# SigfoxTracker.net
KiCad netlist of a schematic drawn in EAGLE
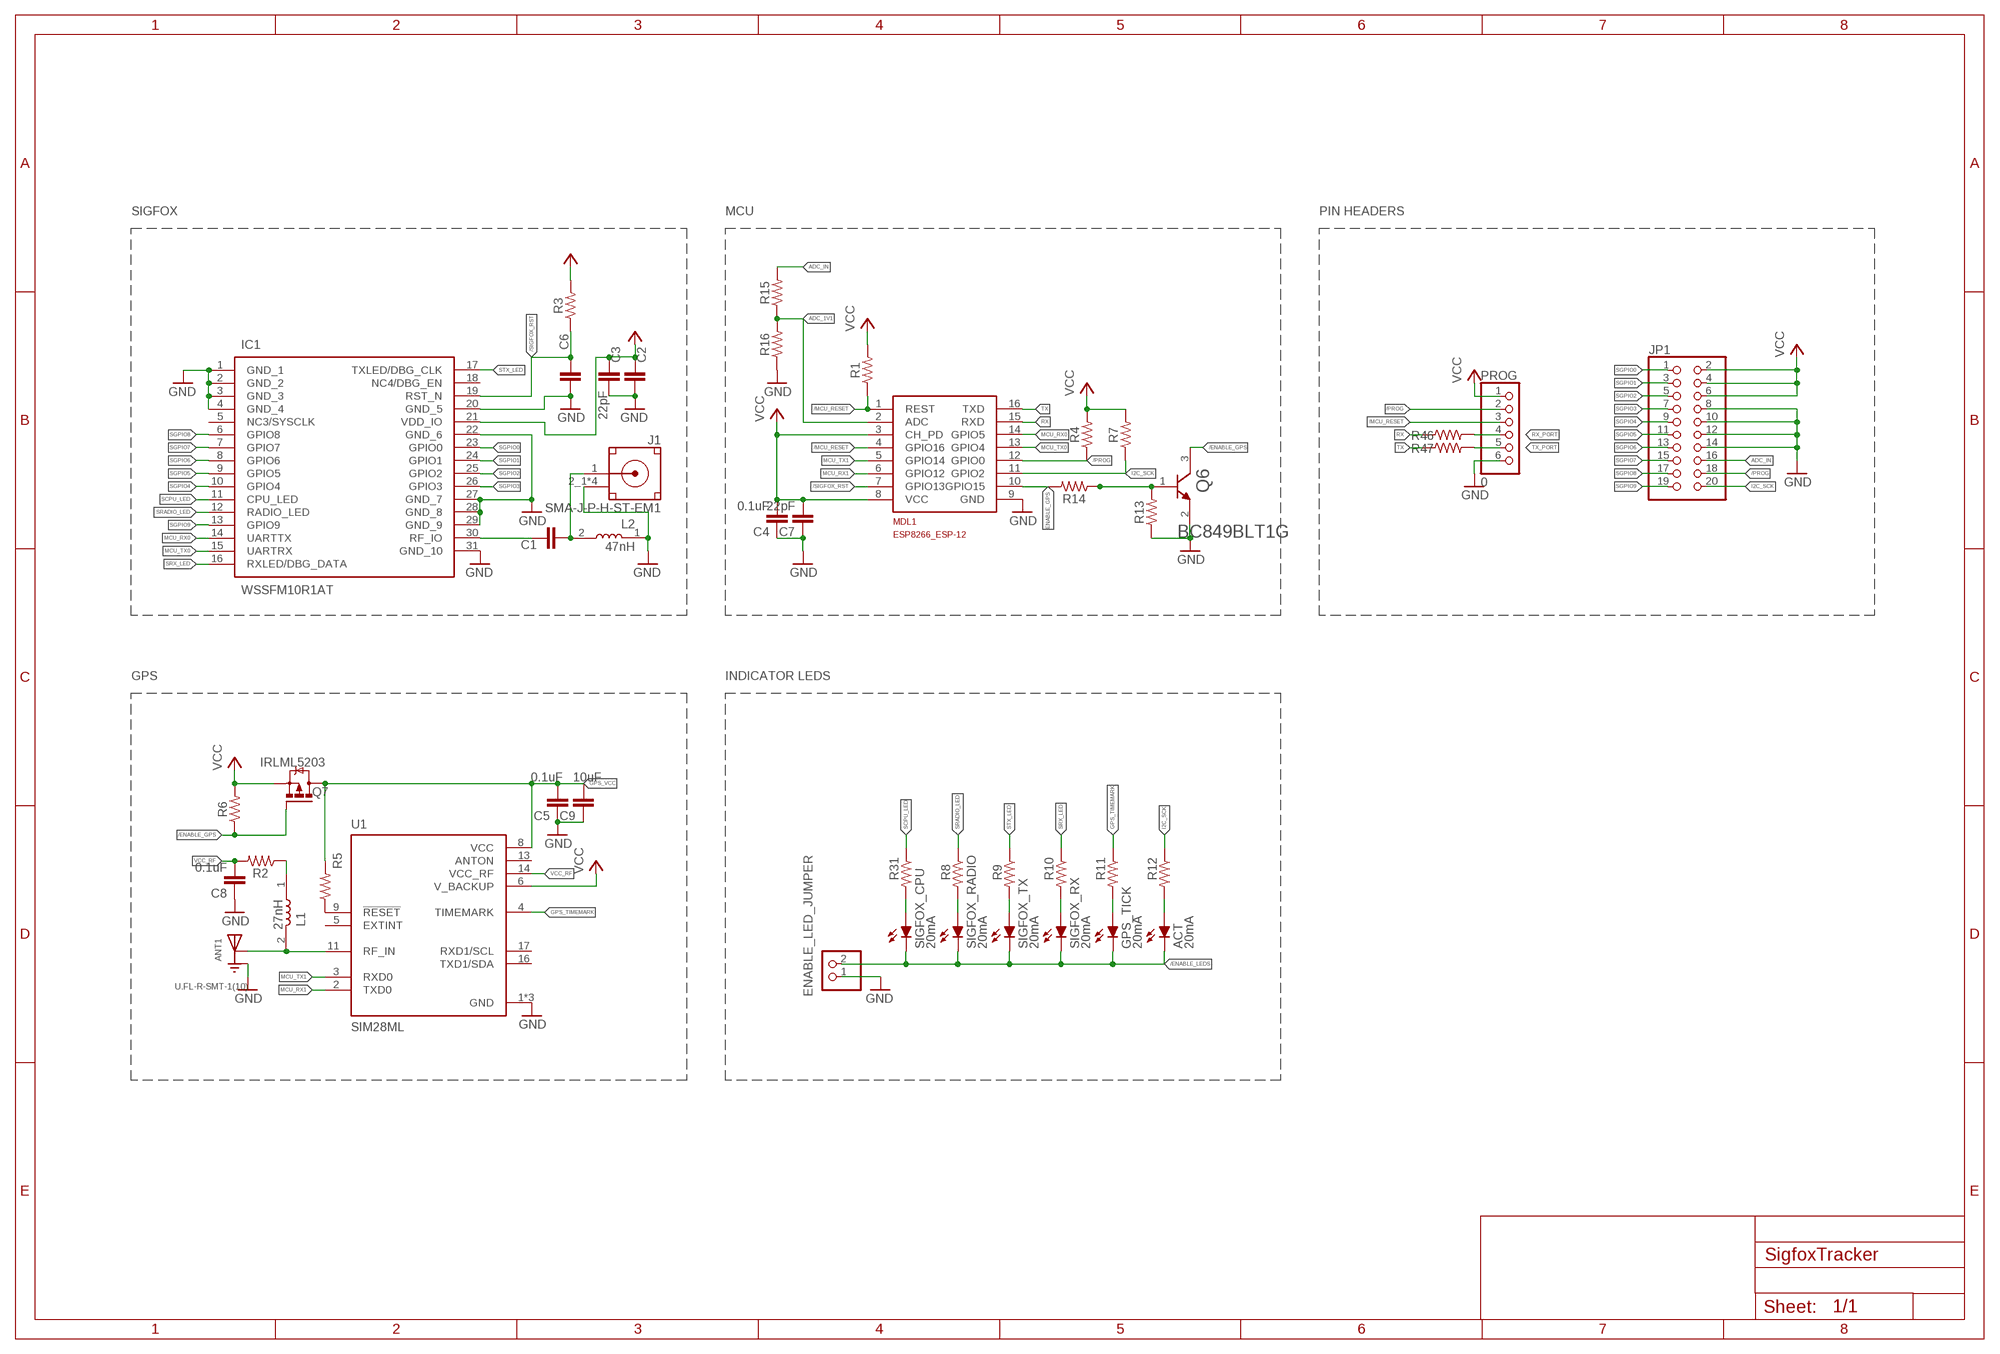
[diagram p0: schematic, sheet 1]

(export (version "E")
  (design (tool "Eeschema 10.0.6"))
  (components
    (comp (ref "ACT")
      (value "20mA")
      (footprint "eagle-import:LED_CHIP-LED0603MP")
      (libsource (lib "eagle-import") (part "LED_LEDCHIP-LED0603MP"))
    )
    (comp (ref "ANT1")
      (value "U.FL-R-SMT-1(10)")
      (footprint "eagle-import:HRS_U.FL-R-SMT-1(10)")
      (fields (field (name "MF") "Hirose") (field (name "MP") "U.FL-R-SMT-1_10_"))
      (libsource (lib "eagle-import") (part "U.FL-R-SMT-1(10)"))
    )
    (comp (ref "C1")
      (value "100pF")
      (footprint "eagle-import:C0603")
      (libsource (lib "eagle-import") (part "C-EUC0603"))
    )
    (comp (ref "C2")
      (value "0.1uF")
      (footprint "eagle-import:C0603")
      (libsource (lib "eagle-import") (part "C-EUC0603"))
    )
    (comp (ref "C3")
      (value "22pF")
      (footprint "eagle-import:C0603")
      (libsource (lib "eagle-import") (part "C-EUC0603"))
    )
    (comp (ref "C4")
      (value "0.1uF")
      (footprint "eagle-import:C0603")
      (libsource (lib "eagle-import") (part "C-EUC0603"))
    )
    (comp (ref "C5")
      (value "0.1uF")
      (footprint "eagle-import:C0603")
      (libsource (lib "eagle-import") (part "C-EUC0603"))
    )
    (comp (ref "C6")
      (value "0.1uF")
      (footprint "eagle-import:C0603")
      (libsource (lib "eagle-import") (part "C-EUC0603"))
    )
    (comp (ref "C7")
      (value "22pF")
      (footprint "eagle-import:C0603")
      (libsource (lib "eagle-import") (part "C-EUC0603"))
    )
    (comp (ref "C8")
      (value "0.1uF")
      (footprint "eagle-import:C0603")
      (libsource (lib "eagle-import") (part "C-EUC0603"))
    )
    (comp (ref "C9")
      (value "10uF")
      (footprint "eagle-import:C0603")
      (libsource (lib "eagle-import") (part "C-EUC0603"))
    )
    (comp (ref "ENABLE_LED_JUMPER")
      (value "PINHD-1X2")
      (footprint "eagle-import:1X02")
      (libsource (lib "eagle-import") (part "PINHD-1X2"))
    )
    (comp (ref "GPS_TICK")
      (value "20mA")
      (footprint "eagle-import:LED_CHIP-LED0603MP")
      (libsource (lib "eagle-import") (part "LED_LEDCHIP-LED0603MP"))
    )
    (comp (ref "IC1")
      (value "WSSFM10R1AT")
      (footprint "eagle-import:WSSFM10R1AT")
      (libsource (lib "eagle-import") (part "WSSFM10R1AT"))
    )
    (comp (ref "J1")
      (value "SMA-J-P-H-ST-EM1")
      (footprint "eagle-import:SMA-J-P-H-ST-EM1")
      (fields (field (name "MF") "Samtec"))
      (libsource (lib "eagle-import") (part "SMA-J-P-H-ST-EM1"))
    )
    (comp (ref "JP1")
      (value "PINHD-2X10")
      (footprint "eagle-import:2X10")
      (libsource (lib "eagle-import") (part "PINHD-2X10"))
    )
    (comp (ref "L1")
      (value "27nH")
      (footprint "eagle-import:INDC1005X45")
      (fields (field (name "MF") "Murata") (field (name "MP") "LQG15HN27NJ02D"))
      (libsource (lib "eagle-import") (part "LQG15HN27NJ02D"))
    )
    (comp (ref "L2")
      (value "47nH")
      (footprint "eagle-import:INDC1005X45")
      (fields (field (name "MF") "Murata") (field (name "MP") "LQG15HN27NJ02D"))
      (libsource (lib "eagle-import") (part "LQG15HN27NJ02D"))
    )
    (comp (ref "MDL1")
      (value "MCU")
      (footprint "eagle-import:ESP8266-ESP12")
      (libsource (lib "eagle-import") (part "ESP8266-12GPIO04/05_CORRECTED"))
    )
    (comp (ref "PROG")
      (value "0")
      (footprint "eagle-import:1X06")
      (libsource (lib "eagle-import") (part "PINHD-1X6"))
    )
    (comp (ref "Q6")
      (value "ON_SEMICONDUCTOR_BC849BLT1GON_SEMICONDUCTOR_BC849BLT1G_0_0")
      (footprint "eagle-import:ON_SEMICONDUCTOR_BC849BLT1G_0")
      (fields (field (name "MF") "On Semiconductor") (field (name "MPN") "BC849BLT1G"))
      (libsource (lib "eagle-import") (part "ON_SEMICONDUCTOR_BC849BLT1GON_SEMICONDUCTOR_BC849BLT1G_0_0"))
    )
    (comp (ref "Q7")
      (value "IRLML5203")
      (footprint "eagle-import:MICRO3")
      (libsource (lib "eagle-import") (part "IRLML5203"))
    )
    (comp (ref "R1")
      (value "100k")
      (footprint "eagle-import:52101-101-REV-A_RC-MASTER-SMD_R0603MP")
      (libsource (lib "eagle-import") (part "52101-101-REV-A_RC-MASTER-SMD_R_0603MP"))
    )
    (comp (ref "R2")
      (value "10R")
      (footprint "eagle-import:RC-MASTER-SMD_R0603MP")
      (libsource (lib "eagle-import") (part "RC-MASTER-SMD_R_0603MP"))
    )
    (comp (ref "R3")
      (value "100K")
      (footprint "eagle-import:RC-MASTER-SMD_R0603MP")
      (libsource (lib "eagle-import") (part "RC-MASTER-SMD_R_0603MP"))
    )
    (comp (ref "R4")
      (value "4K7")
      (footprint "eagle-import:52101-101-REV-A_RC-MASTER-SMD_R0603MP")
      (libsource (lib "eagle-import") (part "52101-101-REV-A_RC-MASTER-SMD_R_0603MP"))
    )
    (comp (ref "R5")
      (value "100k")
      (footprint "eagle-import:52101-101-REV-A_RC-MASTER-SMD_R0603MP")
      (libsource (lib "eagle-import") (part "52101-101-REV-A_RC-MASTER-SMD_R_0603MP"))
    )
    (comp (ref "R6")
      (value "100K")
      (footprint "eagle-import:RC-MASTER-SMD_R0603MP")
      (libsource (lib "eagle-import") (part "RC-MASTER-SMD_R_0603MP"))
    )
    (comp (ref "R7")
      (value "4K7")
      (footprint "eagle-import:52101-101-REV-A_RC-MASTER-SMD_R0603MP")
      (libsource (lib "eagle-import") (part "52101-101-REV-A_RC-MASTER-SMD_R_0603MP"))
    )
    (comp (ref "R8")
      (value "1K")
      (footprint "eagle-import:52101-101-REV-A_RC-MASTER-SMD_R0603MP")
      (libsource (lib "eagle-import") (part "52101-101-REV-A_RC-MASTER-SMD_R_0603MP"))
    )
    (comp (ref "R9")
      (value "1K")
      (footprint "eagle-import:52101-101-REV-A_RC-MASTER-SMD_R0603MP")
      (libsource (lib "eagle-import") (part "52101-101-REV-A_RC-MASTER-SMD_R_0603MP"))
    )
    (comp (ref "R10")
      (value "1K")
      (footprint "eagle-import:52101-101-REV-A_RC-MASTER-SMD_R0603MP")
      (libsource (lib "eagle-import") (part "52101-101-REV-A_RC-MASTER-SMD_R_0603MP"))
    )
    (comp (ref "R11")
      (value "1K")
      (footprint "eagle-import:52101-101-REV-A_RC-MASTER-SMD_R0603MP")
      (libsource (lib "eagle-import") (part "52101-101-REV-A_RC-MASTER-SMD_R_0603MP"))
    )
    (comp (ref "R12")
      (value "1K")
      (footprint "eagle-import:52101-101-REV-A_RC-MASTER-SMD_R0603MP")
      (libsource (lib "eagle-import") (part "52101-101-REV-A_RC-MASTER-SMD_R_0603MP"))
    )
    (comp (ref "R13")
      (value "100k")
      (footprint "eagle-import:52101-101-REV-A_RC-MASTER-SMD_R0603MP")
      (libsource (lib "eagle-import") (part "52101-101-REV-A_RC-MASTER-SMD_R_0603MP"))
    )
    (comp (ref "R14")
      (value "1K")
      (footprint "eagle-import:52101-101-REV-A_RC-MASTER-SMD_R0603MP")
      (libsource (lib "eagle-import") (part "52101-101-REV-A_RC-MASTER-SMD_R_0603MP"))
    )
    (comp (ref "R15")
      (value "10K")
      (footprint "eagle-import:52101-101-REV-A_RC-MASTER-SMD_R0603MP")
      (libsource (lib "eagle-import") (part "52101-101-REV-A_RC-MASTER-SMD_R_0603MP"))
    )
    (comp (ref "R16")
      (value "3V3")
      (footprint "eagle-import:52101-101-REV-A_RC-MASTER-SMD_R0603MP")
      (libsource (lib "eagle-import") (part "52101-101-REV-A_RC-MASTER-SMD_R_0603MP"))
    )
    (comp (ref "R31")
      (value "1K")
      (footprint "eagle-import:52101-101-REV-A_RC-MASTER-SMD_R0603MP")
      (libsource (lib "eagle-import") (part "52101-101-REV-A_RC-MASTER-SMD_R_0603MP"))
    )
    (comp (ref "R46")
      (value "20R")
      (footprint "eagle-import:RC-MASTER-SMD_R0603MP")
      (libsource (lib "eagle-import") (part "RC-MASTER-SMD_R_0603MP"))
    )
    (comp (ref "R47")
      (value "20R")
      (footprint "eagle-import:RC-MASTER-SMD_R0603MP")
      (libsource (lib "eagle-import") (part "RC-MASTER-SMD_R_0603MP"))
    )
    (comp (ref "SIGFOX_CPU")
      (value "20mA")
      (footprint "eagle-import:LED_CHIP-LED0603MP")
      (libsource (lib "eagle-import") (part "LED_LEDCHIP-LED0603MP"))
    )
    (comp (ref "SIGFOX_RADIO")
      (value "20mA")
      (footprint "eagle-import:LED_CHIP-LED0603MP")
      (libsource (lib "eagle-import") (part "LED_LEDCHIP-LED0603MP"))
    )
    (comp (ref "SIGFOX_RX")
      (value "20mA")
      (footprint "eagle-import:LED_CHIP-LED0603MP")
      (libsource (lib "eagle-import") (part "LED_LEDCHIP-LED0603MP"))
    )
    (comp (ref "SIGFOX_TX")
      (value "20mA")
      (footprint "eagle-import:LED_CHIP-LED0603MP")
      (libsource (lib "eagle-import") (part "LED_LEDCHIP-LED0603MP"))
    )
    (comp (ref "U1")
      (value "SIM28ML")
      (footprint "eagle-import:XCVR_SIM28ML")
      (fields (field (name "MF") "Simcom"))
      (libsource (lib "eagle-import") (part "SIM28ML"))
    )
  )
  (nets
    (net (code "1") (name "/ANTON") (class "Default")
      (node (ref "U1") (pin "13") (pinfunction "ANTON_13") (pintype "power_in"))
    )
    (net (code "2") (name "ADC_1V1") (class "Default")
      (node (ref "MDL1") (pin "2") (pinfunction "ADC_2") (pintype "bidirectional"))
      (node (ref "R15") (pin "1") (pinfunction "1_1") (pintype "passive"))
      (node (ref "R16") (pin "2") (pinfunction "2_2") (pintype "passive"))
    )
    (net (code "3") (name "ADC_IN") (class "Default")
      (node (ref "JP1") (pin "16") (pinfunction "16_16") (pintype "passive"))
      (node (ref "R15") (pin "2") (pinfunction "2_2") (pintype "passive"))
    )
    (net (code "4") (name "ENABLE_GPS") (class "Default")
      (node (ref "MDL1") (pin "10") (pinfunction "GPIO15_10") (pintype "bidirectional"))
      (node (ref "R14") (pin "2") (pinfunction "2_2") (pintype "passive"))
    )
    (net (code "5") (name "GND") (class "Default")
      (node (ref "ANT1") (pin "1") (pinfunction "GND_1") (pintype "passive"))
      (node (ref "ANT1") (pin "3") (pinfunction "GND_3") (pintype "passive"))
      (node (ref "C2") (pin "1") (pinfunction "1_1") (pintype "passive"))
      (node (ref "C3") (pin "1") (pinfunction "1_1") (pintype "passive"))
      (node (ref "C4") (pin "1") (pinfunction "1_1") (pintype "passive"))
      (node (ref "C5") (pin "1") (pinfunction "1_1") (pintype "passive"))
      (node (ref "C6") (pin "2") (pinfunction "2_2") (pintype "passive"))
      (node (ref "C7") (pin "1") (pinfunction "1_1") (pintype "passive"))
      (node (ref "C8") (pin "1") (pinfunction "1_1") (pintype "passive"))
      (node (ref "C9") (pin "1") (pinfunction "1_1") (pintype "passive"))
      (node (ref "ENABLE_LED_JUMPER") (pin "1") (pinfunction "1_1") (pintype "passive"))
      (node (ref "IC1") (pin "1") (pinfunction "GND_1_1") (pintype "bidirectional"))
      (node (ref "IC1") (pin "2") (pinfunction "GND_2_2") (pintype "bidirectional"))
      (node (ref "IC1") (pin "20") (pinfunction "GND_5_20") (pintype "bidirectional"))
      (node (ref "IC1") (pin "22") (pinfunction "GND_6_22") (pintype "bidirectional"))
      (node (ref "IC1") (pin "27") (pinfunction "GND_7_27") (pintype "bidirectional"))
      (node (ref "IC1") (pin "28") (pinfunction "GND_8_28") (pintype "bidirectional"))
      (node (ref "IC1") (pin "29") (pinfunction "GND_9_29") (pintype "bidirectional"))
      (node (ref "IC1") (pin "3") (pinfunction "GND_3_3") (pintype "bidirectional"))
      (node (ref "IC1") (pin "31") (pinfunction "GND_10_31") (pintype "bidirectional"))
      (node (ref "IC1") (pin "4") (pinfunction "GND_4_4") (pintype "bidirectional"))
      (node (ref "J1") (pin "2_1") (pinfunction "GND_2_1") (pintype "power_in"))
      (node (ref "J1") (pin "2_2") (pinfunction "GND_2_2") (pintype "power_in"))
      (node (ref "J1") (pin "3_1") (pinfunction "GND_3_1") (pintype "power_in"))
      (node (ref "J1") (pin "3_2") (pinfunction "GND_3_2") (pintype "power_in"))
      (node (ref "JP1") (pin "10") (pinfunction "10_10") (pintype "passive"))
      (node (ref "JP1") (pin "12") (pinfunction "12_12") (pintype "passive"))
      (node (ref "JP1") (pin "14") (pinfunction "14_14") (pintype "passive"))
      (node (ref "JP1") (pin "8") (pinfunction "8_8") (pintype "passive"))
      (node (ref "L2") (pin "1") (pinfunction "1_1") (pintype "passive"))
      (node (ref "MDL1") (pin "9") (pinfunction "GND_9") (pintype "bidirectional"))
      (node (ref "PROG") (pin "6") (pinfunction "6_6") (pintype "passive"))
      (node (ref "Q6") (pin "2") (pinfunction "E_2") (pintype "passive"))
      (node (ref "R13") (pin "1") (pinfunction "1_1") (pintype "passive"))
      (node (ref "R16") (pin "1") (pinfunction "1_1") (pintype "passive"))
      (node (ref "U1") (pin "1") (pinfunction "GND_1") (pintype "power_in"))
      (node (ref "U1") (pin "10") (pinfunction "GND_10") (pintype "power_in"))
      (node (ref "U1") (pin "12") (pinfunction "GND_12") (pintype "power_in"))
    )
    (net (code "6") (name "GPS_TIMEMARK") (class "Default")
      (node (ref "R11") (pin "1") (pinfunction "1_1") (pintype "passive"))
      (node (ref "U1") (pin "4") (pinfunction "TIMEMARK_4") (pintype "output"))
    )
    (net (code "7") (name "GPS_VCC") (class "Default")
      (node (ref "C5") (pin "2") (pinfunction "2_2") (pintype "passive"))
      (node (ref "C9") (pin "2") (pinfunction "2_2") (pintype "passive"))
      (node (ref "Q7") (pin "3") (pinfunction "D_3") (pintype "passive"))
      (node (ref "R5") (pin "2") (pinfunction "2_2") (pintype "passive"))
      (node (ref "U1") (pin "8") (pinfunction "VCC_8") (pintype "power_in"))
    )
    (net (code "8") (name "I2C_SCK") (class "Default")
      (node (ref "JP1") (pin "20") (pinfunction "20_20") (pintype "passive"))
      (node (ref "MDL1") (pin "11") (pinfunction "GPIO2_11") (pintype "bidirectional"))
      (node (ref "R12") (pin "1") (pinfunction "1_1") (pintype "passive"))
      (node (ref "R7") (pin "1") (pinfunction "1_1") (pintype "passive"))
    )
    (net (code "9") (name "MCU_RX0") (class "Default")
      (node (ref "IC1") (pin "14") (pinfunction "UARTTX_14") (pintype "bidirectional"))
      (node (ref "MDL1") (pin "14") (pinfunction "GPIO5_14") (pintype "bidirectional"))
    )
    (net (code "10") (name "MCU_RX1") (class "Default")
      (node (ref "MDL1") (pin "6") (pinfunction "GPIO12_6") (pintype "bidirectional"))
      (node (ref "U1") (pin "2") (pinfunction "TXD0_2") (pintype "output"))
    )
    (net (code "11") (name "MCU_TX0") (class "Default")
      (node (ref "IC1") (pin "15") (pinfunction "UARTRX_15") (pintype "bidirectional"))
      (node (ref "MDL1") (pin "13") (pinfunction "GPIO4_13") (pintype "bidirectional"))
    )
    (net (code "12") (name "MCU_TX1") (class "Default")
      (node (ref "MDL1") (pin "5") (pinfunction "GPIO14_5") (pintype "bidirectional"))
      (node (ref "U1") (pin "3") (pinfunction "RXD0_3") (pintype "input"))
    )
    (net (code "13") (name "Net-(ACT-PadA)") (class "Default")
      (node (ref "ACT") (pin "A") (pinfunction "A_A") (pintype "passive"))
      (node (ref "R12") (pin "2") (pinfunction "2_2") (pintype "passive"))
    )
    (net (code "14") (name "Net-(ANT1-SIG)") (class "Default")
      (node (ref "ANT1") (pin "2") (pinfunction "SIG_2") (pintype "passive"))
      (node (ref "L1") (pin "2") (pinfunction "2_2") (pintype "passive"))
      (node (ref "U1") (pin "11") (pinfunction "RF_IN_11") (pintype "input"))
    )
    (net (code "15") (name "Net-(GPS_TICK-PadA)") (class "Default")
      (node (ref "GPS_TICK") (pin "A") (pinfunction "A_A") (pintype "passive"))
      (node (ref "R11") (pin "2") (pinfunction "2_2") (pintype "passive"))
    )
    (net (code "16") (name "Net-(IC1-RF_IO)") (class "Default")
      (node (ref "C1") (pin "1") (pinfunction "1_1") (pintype "passive"))
      (node (ref "IC1") (pin "30") (pinfunction "RF_IO_30") (pintype "bidirectional"))
    )
    (net (code "17") (name "Net-(J1-SIGNAL)") (class "Default")
      (node (ref "C1") (pin "2") (pinfunction "2_2") (pintype "passive"))
      (node (ref "J1") (pin "1") (pinfunction "SIGNAL_1") (pintype "passive"))
      (node (ref "L2") (pin "2") (pinfunction "2_2") (pintype "passive"))
    )
    (net (code "18") (name "Net-(L1-Pad1)") (class "Default")
      (node (ref "L1") (pin "1") (pinfunction "1_1") (pintype "passive"))
      (node (ref "R2") (pin "1") (pinfunction "1_1") (pintype "passive"))
    )
    (net (code "19") (name "Net-(Q6-B)") (class "Default")
      (node (ref "Q6") (pin "1") (pinfunction "B_1") (pintype "passive"))
      (node (ref "R13") (pin "2") (pinfunction "2_2") (pintype "passive"))
      (node (ref "R14") (pin "1") (pinfunction "1_1") (pintype "passive"))
    )
    (net (code "20") (name "Net-(R8-Pad2)") (class "Default")
      (node (ref "R8") (pin "2") (pinfunction "2_2") (pintype "passive"))
      (node (ref "SIGFOX_RADIO") (pin "A") (pinfunction "A_A") (pintype "passive"))
    )
    (net (code "21") (name "Net-(R9-Pad2)") (class "Default")
      (node (ref "R9") (pin "2") (pinfunction "2_2") (pintype "passive"))
      (node (ref "SIGFOX_TX") (pin "A") (pinfunction "A_A") (pintype "passive"))
    )
    (net (code "22") (name "Net-(R10-Pad2)") (class "Default")
      (node (ref "R10") (pin "2") (pinfunction "2_2") (pintype "passive"))
      (node (ref "SIGFOX_RX") (pin "A") (pinfunction "A_A") (pintype "passive"))
    )
    (net (code "23") (name "Net-(R31-Pad2)") (class "Default")
      (node (ref "R31") (pin "2") (pinfunction "2_2") (pintype "passive"))
      (node (ref "SIGFOX_CPU") (pin "A") (pinfunction "A_A") (pintype "passive"))
    )
    (net (code "24") (name "Net-(U1-~{RESET})") (class "Default")
      (node (ref "R5") (pin "1") (pinfunction "1_1") (pintype "passive"))
      (node (ref "U1") (pin "9") (pinfunction "~{RESET}_9") (pintype "input"))
    )
    (net (code "25") (name "RX") (class "Default")
      (node (ref "MDL1") (pin "15") (pinfunction "RXD_15") (pintype "bidirectional"))
      (node (ref "R46") (pin "1") (pinfunction "1_1") (pintype "passive"))
    )
    (net (code "26") (name "RX_PORT") (class "Default")
      (node (ref "PROG") (pin "4") (pinfunction "4_4") (pintype "passive"))
      (node (ref "R46") (pin "2") (pinfunction "2_2") (pintype "passive"))
    )
    (net (code "27") (name "SCPU_LED") (class "Default")
      (node (ref "IC1") (pin "11") (pinfunction "CPU_LED_11") (pintype "bidirectional"))
      (node (ref "R31") (pin "1") (pinfunction "1_1") (pintype "passive"))
    )
    (net (code "28") (name "SGPIO0") (class "Default")
      (node (ref "IC1") (pin "23") (pinfunction "GPIO0_23") (pintype "bidirectional"))
      (node (ref "JP1") (pin "1") (pinfunction "1_1") (pintype "passive"))
    )
    (net (code "29") (name "SGPIO1") (class "Default")
      (node (ref "IC1") (pin "24") (pinfunction "GPIO1_24") (pintype "bidirectional"))
      (node (ref "JP1") (pin "3") (pinfunction "3_3") (pintype "passive"))
    )
    (net (code "30") (name "SGPIO2") (class "Default")
      (node (ref "IC1") (pin "25") (pinfunction "GPIO2_25") (pintype "bidirectional"))
      (node (ref "JP1") (pin "5") (pinfunction "5_5") (pintype "passive"))
    )
    (net (code "31") (name "SGPIO3") (class "Default")
      (node (ref "IC1") (pin "26") (pinfunction "GPIO3_26") (pintype "bidirectional"))
      (node (ref "JP1") (pin "7") (pinfunction "7_7") (pintype "passive"))
    )
    (net (code "32") (name "SGPIO4") (class "Default")
      (node (ref "IC1") (pin "10") (pinfunction "GPIO4_10") (pintype "bidirectional"))
      (node (ref "JP1") (pin "9") (pinfunction "9_9") (pintype "passive"))
    )
    (net (code "33") (name "SGPIO5") (class "Default")
      (node (ref "IC1") (pin "9") (pinfunction "GPIO5_9") (pintype "bidirectional"))
      (node (ref "JP1") (pin "11") (pinfunction "11_11") (pintype "passive"))
    )
    (net (code "34") (name "SGPIO6") (class "Default")
      (node (ref "IC1") (pin "8") (pinfunction "GPIO6_8") (pintype "bidirectional"))
      (node (ref "JP1") (pin "13") (pinfunction "13_13") (pintype "passive"))
    )
    (net (code "35") (name "SGPIO7") (class "Default")
      (node (ref "IC1") (pin "7") (pinfunction "GPIO7_7") (pintype "bidirectional"))
      (node (ref "JP1") (pin "15") (pinfunction "15_15") (pintype "passive"))
    )
    (net (code "36") (name "SGPIO8") (class "Default")
      (node (ref "IC1") (pin "6") (pinfunction "GPIO8_6") (pintype "bidirectional"))
      (node (ref "JP1") (pin "17") (pinfunction "17_17") (pintype "passive"))
    )
    (net (code "37") (name "SGPIO9") (class "Default")
      (node (ref "IC1") (pin "13") (pinfunction "GPIO9_13") (pintype "bidirectional"))
      (node (ref "JP1") (pin "19") (pinfunction "19_19") (pintype "passive"))
    )
    (net (code "38") (name "SRADIO_LED") (class "Default")
      (node (ref "IC1") (pin "12") (pinfunction "RADIO_LED_12") (pintype "bidirectional"))
      (node (ref "R8") (pin "1") (pinfunction "1_1") (pintype "passive"))
    )
    (net (code "39") (name "SRX_LED") (class "Default")
      (node (ref "IC1") (pin "16") (pinfunction "RXLED/DBG_DATA_16") (pintype "bidirectional"))
      (node (ref "R10") (pin "1") (pinfunction "1_1") (pintype "passive"))
    )
    (net (code "40") (name "STX_LED") (class "Default")
      (node (ref "IC1") (pin "17") (pinfunction "TXLED/DBG_CLK_17") (pintype "bidirectional"))
      (node (ref "R9") (pin "1") (pinfunction "1_1") (pintype "passive"))
    )
    (net (code "41") (name "TX") (class "Default")
      (node (ref "MDL1") (pin "16") (pinfunction "TXD_16") (pintype "bidirectional"))
      (node (ref "R47") (pin "1") (pinfunction "1_1") (pintype "passive"))
    )
    (net (code "42") (name "TX_PORT") (class "Default")
      (node (ref "PROG") (pin "5") (pinfunction "5_5") (pintype "passive"))
      (node (ref "R47") (pin "2") (pinfunction "2_2") (pintype "passive"))
    )
    (net (code "43") (name "VCC") (class "Default")
      (node (ref "C2") (pin "2") (pinfunction "2_2") (pintype "passive"))
      (node (ref "C3") (pin "2") (pinfunction "2_2") (pintype "passive"))
      (node (ref "C4") (pin "2") (pinfunction "2_2") (pintype "passive"))
      (node (ref "C7") (pin "2") (pinfunction "2_2") (pintype "passive"))
      (node (ref "IC1") (pin "21") (pinfunction "VDD_IO_21") (pintype "bidirectional"))
      (node (ref "JP1") (pin "2") (pinfunction "2_2") (pintype "passive"))
      (node (ref "JP1") (pin "4") (pinfunction "4_4") (pintype "passive"))
      (node (ref "JP1") (pin "6") (pinfunction "6_6") (pintype "passive"))
      (node (ref "MDL1") (pin "3") (pinfunction "CH_PD_3") (pintype "bidirectional"))
      (node (ref "MDL1") (pin "8") (pinfunction "VCC_8") (pintype "bidirectional"))
      (node (ref "PROG") (pin "1") (pinfunction "1_1") (pintype "passive"))
      (node (ref "Q7") (pin "2") (pinfunction "S_2") (pintype "passive"))
      (node (ref "R1") (pin "2") (pinfunction "2_2") (pintype "passive"))
      (node (ref "R3") (pin "2") (pinfunction "2_2") (pintype "passive"))
      (node (ref "R4") (pin "2") (pinfunction "2_2") (pintype "passive"))
      (node (ref "R6") (pin "2") (pinfunction "2_2") (pintype "passive"))
      (node (ref "R7") (pin "2") (pinfunction "2_2") (pintype "passive"))
      (node (ref "U1") (pin "6") (pinfunction "V_BACKUP_6") (pintype "power_in"))
    )
    (net (code "44") (name "VCC_RF") (class "Default")
      (node (ref "C8") (pin "2") (pinfunction "2_2") (pintype "passive"))
      (node (ref "R2") (pin "2") (pinfunction "2_2") (pintype "passive"))
      (node (ref "U1") (pin "14") (pinfunction "VCC_RF_14") (pintype "power_in"))
    )
    (net (code "45") (name "unconnected-(IC1-NC3{slash}SYSCLK-Pad5)") (class "Default")
      (node (ref "IC1") (pin "5") (pinfunction "NC3/SYSCLK_5") (pintype "bidirectional"))
    )
    (net (code "46") (name "unconnected-(IC1-NC4{slash}DBG_EN-Pad18)") (class "Default")
      (node (ref "IC1") (pin "18") (pinfunction "NC4/DBG_EN_18") (pintype "bidirectional"))
    )
    (net (code "47") (name "unconnected-(U1-EXTINT-Pad5)") (class "Default")
      (node (ref "U1") (pin "5") (pinfunction "EXTINT_5") (pintype "input"))
    )
    (net (code "48") (name "unconnected-(U1-RXD1{slash}SCL-Pad17)") (class "Default")
      (node (ref "U1") (pin "17") (pinfunction "RXD1/SCL_17") (pintype "input"))
    )
    (net (code "49") (name "unconnected-(U1-TXD1{slash}SDA-Pad16)") (class "Default")
      (node (ref "U1") (pin "16") (pinfunction "TXD1/SDA_16") (pintype "bidirectional"))
    )
    (net (code "50") (name "{slash}ENABLE_GPS") (class "Default")
      (node (ref "Q6") (pin "3") (pinfunction "C_3") (pintype "passive"))
      (node (ref "Q7") (pin "1") (pinfunction "G_1") (pintype "passive"))
      (node (ref "R6") (pin "1") (pinfunction "1_1") (pintype "passive"))
    )
    (net (code "51") (name "{slash}ENABLE_LEDS") (class "Default")
      (node (ref "ACT") (pin "C") (pinfunction "C_C") (pintype "passive"))
      (node (ref "ENABLE_LED_JUMPER") (pin "2") (pinfunction "2_2") (pintype "passive"))
      (node (ref "GPS_TICK") (pin "C") (pinfunction "C_C") (pintype "passive"))
      (node (ref "SIGFOX_CPU") (pin "C") (pinfunction "C_C") (pintype "passive"))
      (node (ref "SIGFOX_RADIO") (pin "C") (pinfunction "C_C") (pintype "passive"))
      (node (ref "SIGFOX_RX") (pin "C") (pinfunction "C_C") (pintype "passive"))
      (node (ref "SIGFOX_TX") (pin "C") (pinfunction "C_C") (pintype "passive"))
    )
    (net (code "52") (name "{slash}MCU_RESET") (class "Default")
      (node (ref "MDL1") (pin "1") (pinfunction "REST_1") (pintype "bidirectional"))
      (node (ref "MDL1") (pin "4") (pinfunction "GPIO16_4") (pintype "bidirectional"))
      (node (ref "PROG") (pin "3") (pinfunction "3_3") (pintype "passive"))
      (node (ref "R1") (pin "1") (pinfunction "1_1") (pintype "passive"))
    )
    (net (code "53") (name "{slash}PROG") (class "Default")
      (node (ref "JP1") (pin "18") (pinfunction "18_18") (pintype "passive"))
      (node (ref "MDL1") (pin "12") (pinfunction "GPIO0_12") (pintype "bidirectional"))
      (node (ref "PROG") (pin "2") (pinfunction "2_2") (pintype "passive"))
      (node (ref "R4") (pin "1") (pinfunction "1_1") (pintype "passive"))
    )
    (net (code "54") (name "{slash}SIGFOX_RST") (class "Default")
      (node (ref "C6") (pin "1") (pinfunction "1_1") (pintype "passive"))
      (node (ref "IC1") (pin "19") (pinfunction "RST_N_19") (pintype "bidirectional"))
      (node (ref "MDL1") (pin "7") (pinfunction "GPIO13_7") (pintype "bidirectional"))
      (node (ref "R3") (pin "1") (pinfunction "1_1") (pintype "passive"))
    )
  )
)
